# sidepcb15-03.net
KiCad netlist of a schematic drawn in EAGLE
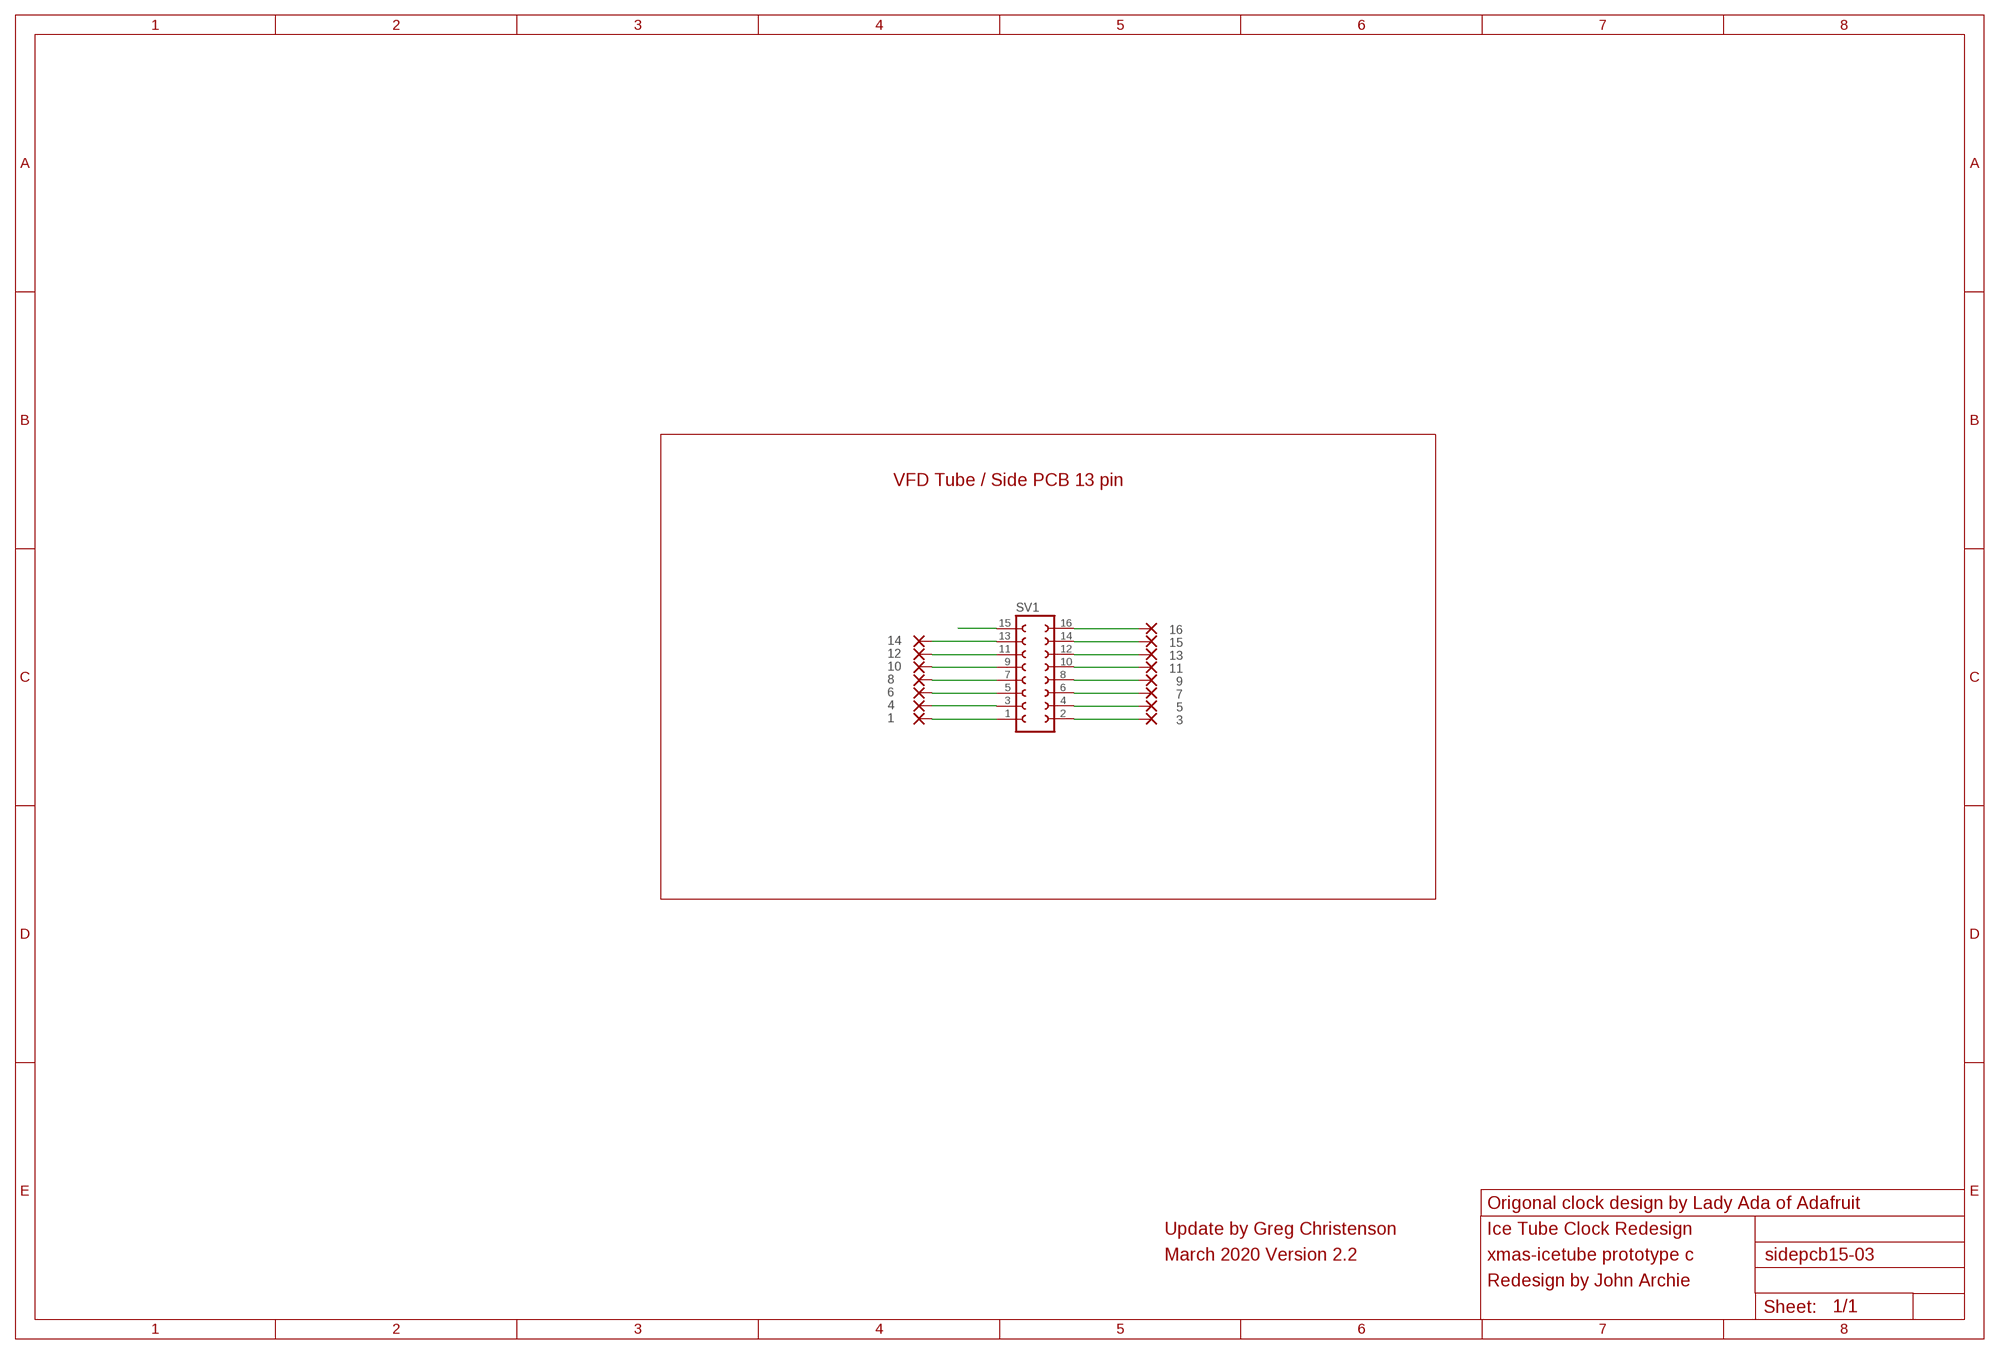
[diagram p0: schematic, sheet 1]

(export (version "E")
  (design (tool "Eeschema 10.0.6"))
  (components
    (comp (ref "1")
      (value "1,6/0,8")
      (footprint "eagle-import:1,6_0,8")
      (libsource (lib "eagle-import") (part "1,6/0,8"))
    )
    (comp (ref "3")
      (value "1,6/0,8")
      (footprint "eagle-import:1,6_0,8")
      (libsource (lib "eagle-import") (part "1,6/0,8"))
    )
    (comp (ref "4")
      (value "1,6/0,8")
      (footprint "eagle-import:1,6_0,8")
      (libsource (lib "eagle-import") (part "1,6/0,8"))
    )
    (comp (ref "5")
      (value "1,6/0,8")
      (footprint "eagle-import:1,6_0,8")
      (libsource (lib "eagle-import") (part "1,6/0,8"))
    )
    (comp (ref "6")
      (value "1,6/0,8")
      (footprint "eagle-import:1,6_0,8")
      (libsource (lib "eagle-import") (part "1,6/0,8"))
    )
    (comp (ref "7")
      (value "1,6/0,8")
      (footprint "eagle-import:1,6_0,8")
      (libsource (lib "eagle-import") (part "1,6/0,8"))
    )
    (comp (ref "8")
      (value "1,6/0,8")
      (footprint "eagle-import:1,6_0,8")
      (libsource (lib "eagle-import") (part "1,6/0,8"))
    )
    (comp (ref "9")
      (value "1,6/0,8")
      (footprint "eagle-import:1,6_0,8")
      (libsource (lib "eagle-import") (part "1,6/0,8"))
    )
    (comp (ref "10")
      (value "1,6/0,8")
      (footprint "eagle-import:1,6_0,8")
      (libsource (lib "eagle-import") (part "1,6/0,8"))
    )
    (comp (ref "11")
      (value "1,6/0,8")
      (footprint "eagle-import:1,6_0,8")
      (libsource (lib "eagle-import") (part "1,6/0,8"))
    )
    (comp (ref "12")
      (value "1,6/0,8")
      (footprint "eagle-import:1,6_0,8")
      (libsource (lib "eagle-import") (part "1,6/0,8"))
    )
    (comp (ref "13")
      (value "1,6/0,8")
      (footprint "eagle-import:1,6_0,8")
      (libsource (lib "eagle-import") (part "1,6/0,8"))
    )
    (comp (ref "14")
      (value "1,6/0,8")
      (footprint "eagle-import:1,6_0,8")
      (libsource (lib "eagle-import") (part "1,6/0,8"))
    )
    (comp (ref "15")
      (value "1,6/0,8")
      (footprint "eagle-import:1,6_0,8")
      (libsource (lib "eagle-import") (part "1,6/0,8"))
    )
    (comp (ref "16")
      (value "1,6/0,8")
      (footprint "eagle-import:1,6_0,8")
      (libsource (lib "eagle-import") (part "1,6/0,8"))
    )
    (comp (ref "SV1")
      (value "FE08-2W")
      (footprint "eagle-import:FE08-2W")
      (libsource (lib "eagle-import") (part "FE08-2W"))
    )
  )
  (nets
    (net (code "1") (name "Net-(1-P)") (class "Default")
      (node (ref "1") (pin "1") (pinfunction "P_1") (pintype "passive"))
      (node (ref "SV1") (pin "1") (pinfunction "1_1") (pintype "passive"))
    )
    (net (code "2") (name "Net-(3-P)") (class "Default")
      (node (ref "3") (pin "1") (pinfunction "P_1") (pintype "passive"))
      (node (ref "SV1") (pin "2") (pinfunction "2_2") (pintype "passive"))
    )
    (net (code "3") (name "Net-(4-P)") (class "Default")
      (node (ref "4") (pin "1") (pinfunction "P_1") (pintype "passive"))
      (node (ref "SV1") (pin "3") (pinfunction "3_3") (pintype "passive"))
    )
    (net (code "4") (name "Net-(5-P)") (class "Default")
      (node (ref "5") (pin "1") (pinfunction "P_1") (pintype "passive"))
      (node (ref "SV1") (pin "4") (pinfunction "4_4") (pintype "passive"))
    )
    (net (code "5") (name "Net-(6-P)") (class "Default")
      (node (ref "6") (pin "1") (pinfunction "P_1") (pintype "passive"))
      (node (ref "SV1") (pin "5") (pinfunction "5_5") (pintype "passive"))
    )
    (net (code "6") (name "Net-(7-P)") (class "Default")
      (node (ref "7") (pin "1") (pinfunction "P_1") (pintype "passive"))
      (node (ref "SV1") (pin "6") (pinfunction "6_6") (pintype "passive"))
    )
    (net (code "7") (name "Net-(8-P)") (class "Default")
      (node (ref "8") (pin "1") (pinfunction "P_1") (pintype "passive"))
      (node (ref "SV1") (pin "7") (pinfunction "7_7") (pintype "passive"))
    )
    (net (code "8") (name "Net-(9-P)") (class "Default")
      (node (ref "9") (pin "1") (pinfunction "P_1") (pintype "passive"))
      (node (ref "SV1") (pin "8") (pinfunction "8_8") (pintype "passive"))
    )
    (net (code "9") (name "Net-(10-P)") (class "Default")
      (node (ref "10") (pin "1") (pinfunction "P_1") (pintype "passive"))
      (node (ref "SV1") (pin "9") (pinfunction "9_9") (pintype "passive"))
    )
    (net (code "10") (name "Net-(11-P)") (class "Default")
      (node (ref "11") (pin "1") (pinfunction "P_1") (pintype "passive"))
      (node (ref "SV1") (pin "10") (pinfunction "10_10") (pintype "passive"))
    )
    (net (code "11") (name "Net-(12-P)") (class "Default")
      (node (ref "12") (pin "1") (pinfunction "P_1") (pintype "passive"))
      (node (ref "SV1") (pin "11") (pinfunction "11_11") (pintype "passive"))
    )
    (net (code "12") (name "Net-(13-P)") (class "Default")
      (node (ref "13") (pin "1") (pinfunction "P_1") (pintype "passive"))
      (node (ref "SV1") (pin "12") (pinfunction "12_12") (pintype "passive"))
    )
    (net (code "13") (name "Net-(14-P)") (class "Default")
      (node (ref "14") (pin "1") (pinfunction "P_1") (pintype "passive"))
      (node (ref "SV1") (pin "13") (pinfunction "13_13") (pintype "passive"))
    )
    (net (code "14") (name "Net-(15-P)") (class "Default")
      (node (ref "15") (pin "1") (pinfunction "P_1") (pintype "passive"))
      (node (ref "SV1") (pin "14") (pinfunction "14_14") (pintype "passive"))
    )
    (net (code "15") (name "Net-(16-P)") (class "Default")
      (node (ref "16") (pin "1") (pinfunction "P_1") (pintype "passive"))
      (node (ref "SV1") (pin "16") (pinfunction "16_16") (pintype "passive"))
    )
    (net (code "16") (name "unconnected-(SV1-Pad15)") (class "Default")
      (node (ref "SV1") (pin "15") (pinfunction "15_15") (pintype "passive"))
    )
  )
)
